# T5400_Barometer_Breakout-v1.net
KiCad netlist of a schematic drawn in EAGLE
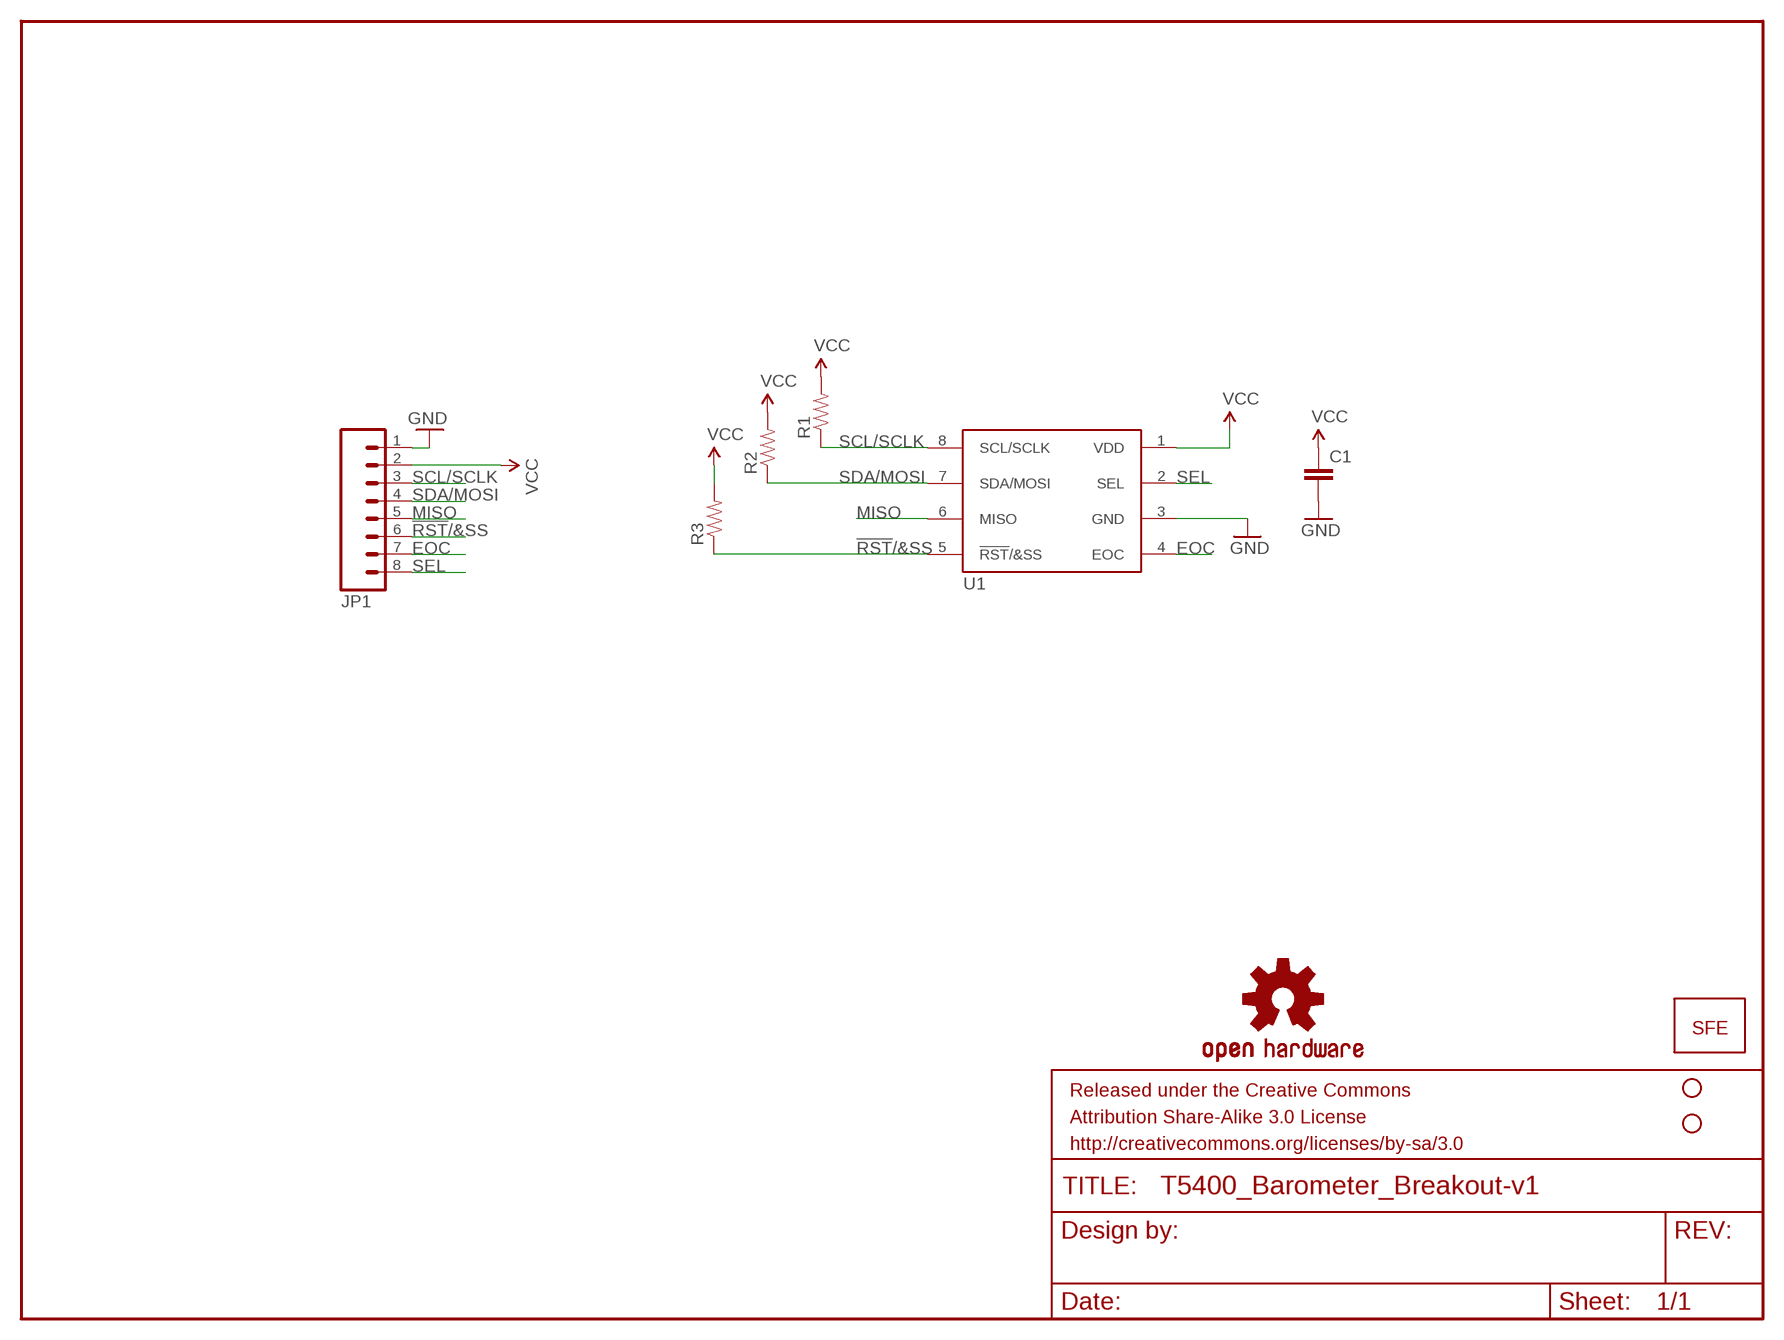
[diagram p0: schematic, sheet 1]

(export (version "E")
  (design (tool "Eeschema 10.0.6"))
  (components
    (comp (ref "C1")
      (value "0.1UF-25V-5%(0603)")
      (footprint "eagle-import:0603-CAP")
      (libsource (lib "eagle-import") (part "0.1UF-25V-5%(0603)"))
    )
    (comp (ref "FRAME1")
      (value "FRAME-LETTE")
      (footprint "eagle-import:CREATIVE_COMMONS")
      (libsource (lib "eagle-import") (part "FRAME-LETTER"))
    )
    (comp (ref "JP1")
      (value "M081X08")
      (footprint "eagle-import:1X08")
      (libsource (lib "eagle-import") (part "M081X08"))
    )
    (comp (ref "LOGO1")
      (value "LOGO-SFENEW")
      (footprint "eagle-import:SFE-NEW-WEBLOGO")
      (libsource (lib "eagle-import") (part "LOGO-SFENEW"))
    )
    (comp (ref "LOGO2")
      (value "OSHW-LOGOS")
      (footprint "eagle-import:OSHW-LOGO-S")
      (libsource (lib "eagle-import") (part "OSHW-LOGOS"))
    )
    (comp (ref "R1")
      (value "RESISTOR0603-RES")
      (footprint "eagle-import:0603-RES")
      (libsource (lib "eagle-import") (part "RESISTOR0603-RES"))
    )
    (comp (ref "R2")
      (value "RESISTOR0603-RES")
      (footprint "eagle-import:0603-RES")
      (libsource (lib "eagle-import") (part "RESISTOR0603-RES"))
    )
    (comp (ref "R3")
      (value "RESISTOR0603-RES")
      (footprint "eagle-import:0603-RES")
      (libsource (lib "eagle-import") (part "RESISTOR0603-RES"))
    )
    (comp (ref "STANDOFF1")
      (value "STAND-OFF")
      (footprint "eagle-import:STAND-OFF")
      (libsource (lib "eagle-import") (part "STAND-OFF"))
    )
    (comp (ref "STANDOFF2")
      (value "STAND-OFF")
      (footprint "eagle-import:STAND-OFF")
      (libsource (lib "eagle-import") (part "STAND-OFF"))
    )
    (comp (ref "U1")
      (value "T5400")
      (footprint "eagle-import:T5400")
      (libsource (lib "eagle-import") (part "T5400"))
    )
  )
  (nets
    (net (code "1") (name "/EOC") (class "Default")
      (node (ref "JP1") (pin "7") (pinfunction "7_7") (pintype "passive"))
      (node (ref "U1") (pin "4") (pinfunction "EOC_4") (pintype "bidirectional"))
    )
    (net (code "2") (name "/MISO") (class "Default")
      (node (ref "JP1") (pin "5") (pinfunction "5_5") (pintype "passive"))
      (node (ref "U1") (pin "6") (pinfunction "MISO_6") (pintype "bidirectional"))
    )
    (net (code "3") (name "/SCL{slash}SCLK") (class "Default")
      (node (ref "JP1") (pin "3") (pinfunction "3_3") (pintype "passive"))
      (node (ref "R1") (pin "1") (pinfunction "1_1") (pintype "passive"))
      (node (ref "U1") (pin "8") (pinfunction "SCL/SCLK_8") (pintype "bidirectional"))
    )
    (net (code "4") (name "/SDA{slash}MOSI") (class "Default")
      (node (ref "JP1") (pin "4") (pinfunction "4_4") (pintype "passive"))
      (node (ref "R2") (pin "1") (pinfunction "1_1") (pintype "passive"))
      (node (ref "U1") (pin "7") (pinfunction "SDA/MOSI_7") (pintype "bidirectional"))
    )
    (net (code "5") (name "/SEL") (class "Default")
      (node (ref "JP1") (pin "8") (pinfunction "8_8") (pintype "passive"))
      (node (ref "U1") (pin "2") (pinfunction "SEL_2") (pintype "bidirectional"))
    )
    (net (code "6") (name "/~{RST}{slash}&SS") (class "Default")
      (node (ref "JP1") (pin "6") (pinfunction "6_6") (pintype "passive"))
      (node (ref "R3") (pin "1") (pinfunction "1_1") (pintype "passive"))
      (node (ref "U1") (pin "5") (pinfunction "~{RST}/&SS_5") (pintype "bidirectional"))
    )
    (net (code "7") (name "GND") (class "Default")
      (node (ref "C1") (pin "2") (pinfunction "2_2") (pintype "passive"))
      (node (ref "JP1") (pin "1") (pinfunction "1_1") (pintype "passive"))
      (node (ref "U1") (pin "3") (pinfunction "GND_3") (pintype "bidirectional"))
    )
    (net (code "8") (name "VCC") (class "Default")
      (node (ref "C1") (pin "1") (pinfunction "1_1") (pintype "passive"))
      (node (ref "JP1") (pin "2") (pinfunction "2_2") (pintype "passive"))
      (node (ref "R1") (pin "2") (pinfunction "2_2") (pintype "passive"))
      (node (ref "R2") (pin "2") (pinfunction "2_2") (pintype "passive"))
      (node (ref "R3") (pin "2") (pinfunction "2_2") (pintype "passive"))
      (node (ref "U1") (pin "1") (pinfunction "VDD_1") (pintype "bidirectional"))
    )
  )
)
